# -3V.net
KiCad netlist of a schematic drawn in EAGLE
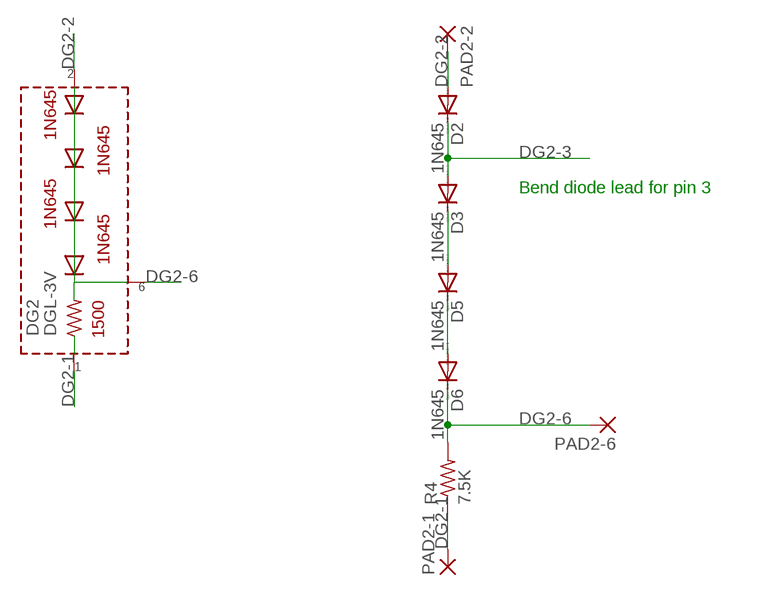
[diagram p0: schematic, sheet 1]

(export (version "E")
  (design (tool "Eeschema 10.0.6"))
  (components
    (comp (ref "D2")
      (value "1N645")
      (footprint "eagle-import:DO34-7")
      (libsource (lib "eagle-import") (part "DIODE-DO34-7"))
    )
    (comp (ref "D3")
      (value "1N645")
      (footprint "eagle-import:DO34-7")
      (libsource (lib "eagle-import") (part "DIODE-DO34-7"))
    )
    (comp (ref "D5")
      (value "1N645")
      (footprint "eagle-import:DO34-7")
      (libsource (lib "eagle-import") (part "DIODE-DO34-7"))
    )
    (comp (ref "D6")
      (value "1N645")
      (footprint "eagle-import:DO34-7")
      (libsource (lib "eagle-import") (part "DIODE-DO34-7"))
    )
    (comp (ref "DG2")
      (value "DGL-3V")
      (footprint "eagle-import:DGL2")
      (libsource (lib "eagle-import") (part "DGL-3V"))
    )
    (comp (ref "PAD2-1")
      (value "1,6/0,8")
      (footprint "eagle-import:1,6_0,8")
      (libsource (lib "eagle-import") (part "1,6/0,8"))
    )
    (comp (ref "PAD2-2")
      (value "1,6/0,8")
      (footprint "eagle-import:1,6_0,8")
      (libsource (lib "eagle-import") (part "1,6/0,8"))
    )
    (comp (ref "PAD2-6")
      (value "1,6/0,8")
      (footprint "eagle-import:1,6_0,8")
      (libsource (lib "eagle-import") (part "1,6/0,8"))
    )
    (comp (ref "R4")
      (value "7.5K")
      (footprint "eagle-import:0207_7")
      (libsource (lib "eagle-import") (part "R-US_0207/7"))
    )
  )
  (nets
    (net (code "1") (name "/DG2-1") (class "Default")
      (node (ref "DG2") (pin "P$1") (pinfunction "1_P$1") (pintype "passive"))
      (node (ref "PAD2-1") (pin "1") (pinfunction "P_1") (pintype "passive"))
      (node (ref "R4") (pin "1") (pinfunction "1_1") (pintype "passive"))
    )
    (net (code "2") (name "/DG2-2") (class "Default")
      (node (ref "D2") (pin "A") (pinfunction "A_A") (pintype "passive"))
      (node (ref "DG2") (pin "P$2") (pinfunction "2_P$2") (pintype "passive"))
      (node (ref "PAD2-2") (pin "1") (pinfunction "P_1") (pintype "passive"))
    )
    (net (code "3") (name "/DG2-3") (class "Default")
      (node (ref "D2") (pin "C") (pinfunction "C_C") (pintype "passive"))
      (node (ref "D3") (pin "A") (pinfunction "A_A") (pintype "passive"))
    )
    (net (code "4") (name "/DG2-6") (class "Default")
      (node (ref "D6") (pin "C") (pinfunction "C_C") (pintype "passive"))
      (node (ref "DG2") (pin "P$6") (pinfunction "6_P$6") (pintype "passive"))
      (node (ref "PAD2-6") (pin "1") (pinfunction "P_1") (pintype "passive"))
      (node (ref "R4") (pin "2") (pinfunction "2_2") (pintype "passive"))
    )
    (net (code "5") (name "Net-(D3-PadC)") (class "Default")
      (node (ref "D3") (pin "C") (pinfunction "C_C") (pintype "passive"))
      (node (ref "D5") (pin "A") (pinfunction "A_A") (pintype "passive"))
    )
    (net (code "6") (name "Net-(D5-PadC)") (class "Default")
      (node (ref "D5") (pin "C") (pinfunction "C_C") (pintype "passive"))
      (node (ref "D6") (pin "A") (pinfunction "A_A") (pintype "passive"))
    )
  )
)
